# Backplane_Reference_R1_0.net
KiCad netlist of a schematic drawn in EAGLE
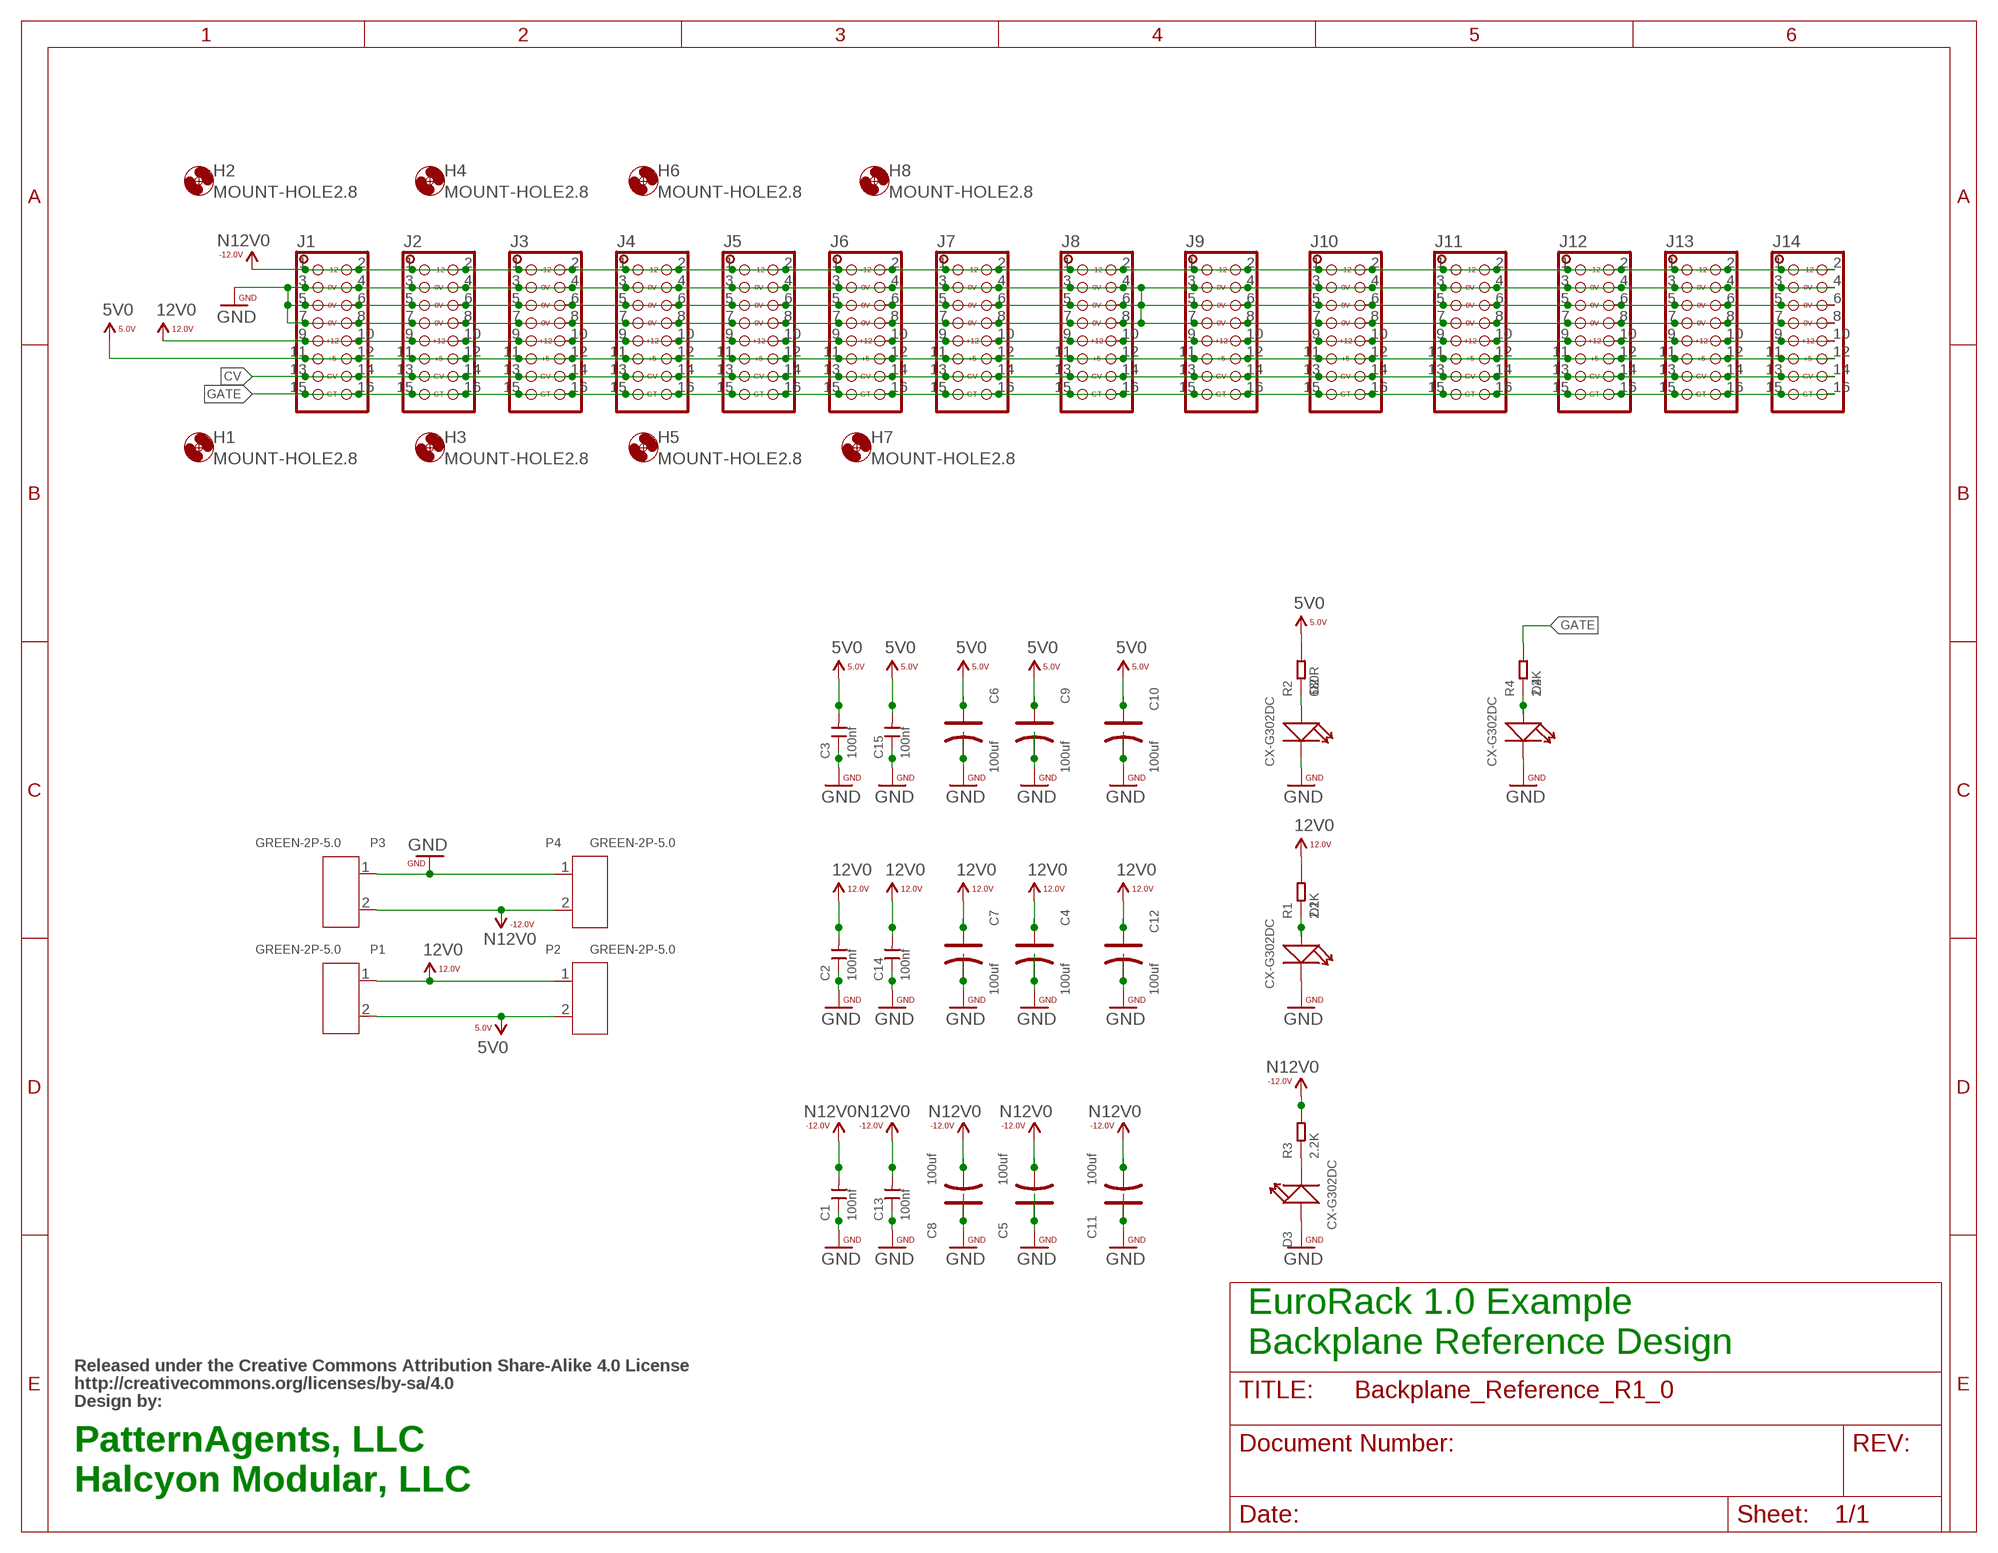
[diagram p0: schematic, sheet 1]

(export (version "E")
  (design (tool "Eeschema 10.0.6"))
  (components
    (comp (ref "C1")
      (value "100nf")
      (footprint "eagle-import:CERAMIC-2.54")
      (fields (field (name "MPN") "CC1-F5SL2A101KSPW"))
      (libsource (lib "eagle-import") (part "DIP-CERAMIC-DISC-100NF-50V-Y5V(D5.0MM)"))
    )
    (comp (ref "C2")
      (value "100nf")
      (footprint "eagle-import:CERAMIC-2.54")
      (fields (field (name "MPN") "CC1-F5SL2A101KSPW"))
      (libsource (lib "eagle-import") (part "DIP-CERAMIC-DISC-100NF-50V-Y5V(D5.0MM)"))
    )
    (comp (ref "C3")
      (value "100nf")
      (footprint "eagle-import:CERAMIC-2.54")
      (fields (field (name "MPN") "CC1-F5SL2A101KSPW"))
      (libsource (lib "eagle-import") (part "DIP-CERAMIC-DISC-100NF-50V-Y5V(D5.0MM)"))
    )
    (comp (ref "C4")
      (value "100uf")
      (footprint "eagle-import:PC-D5.3MM")
      (fields (field (name "MPN") "KS 100uF/16V"))
      (libsource (lib "eagle-import") (part "DIP-ALUMINUM-100UF-16V(D5-H7MM)"))
    )
    (comp (ref "C5")
      (value "100uf")
      (footprint "eagle-import:PC-D5.3MM")
      (fields (field (name "MPN") "KS 100uF/16V"))
      (libsource (lib "eagle-import") (part "DIP-ALUMINUM-100UF-16V(D5-H7MM)"))
    )
    (comp (ref "C6")
      (value "100uf")
      (footprint "eagle-import:PC-D5.3MM")
      (fields (field (name "MPN") "KS 100uF/16V"))
      (libsource (lib "eagle-import") (part "DIP-ALUMINUM-100UF-16V(D5-H7MM)"))
    )
    (comp (ref "C7")
      (value "100uf")
      (footprint "eagle-import:PC-D5.3MM")
      (fields (field (name "MPN") "KS 100uF/16V"))
      (libsource (lib "eagle-import") (part "DIP-ALUMINUM-100UF-16V(D5-H7MM)"))
    )
    (comp (ref "C8")
      (value "100uf")
      (footprint "eagle-import:PC-D5.3MM")
      (fields (field (name "MPN") "KS 100uF/16V"))
      (libsource (lib "eagle-import") (part "DIP-ALUMINUM-100UF-16V(D5-H7MM)"))
    )
    (comp (ref "C9")
      (value "100uf")
      (footprint "eagle-import:PC-D5.3MM")
      (fields (field (name "MPN") "KS 100uF/16V"))
      (libsource (lib "eagle-import") (part "DIP-ALUMINUM-100UF-16V(D5-H7MM)"))
    )
    (comp (ref "C10")
      (value "100uf")
      (footprint "eagle-import:PC-D5.3MM")
      (fields (field (name "MPN") "KS 100uF/16V"))
      (libsource (lib "eagle-import") (part "DIP-ALUMINUM-100UF-16V(D5-H7MM)"))
    )
    (comp (ref "C11")
      (value "100uf")
      (footprint "eagle-import:PC-D5.3MM")
      (fields (field (name "MPN") "KS 100uF/16V"))
      (libsource (lib "eagle-import") (part "DIP-ALUMINUM-100UF-16V(D5-H7MM)"))
    )
    (comp (ref "C12")
      (value "100uf")
      (footprint "eagle-import:PC-D5.3MM")
      (fields (field (name "MPN") "KS 100uF/16V"))
      (libsource (lib "eagle-import") (part "DIP-ALUMINUM-100UF-16V(D5-H7MM)"))
    )
    (comp (ref "C13")
      (value "100nf")
      (footprint "eagle-import:CERAMIC-2.54")
      (fields (field (name "MPN") "CC1-F5SL2A101KSPW"))
      (libsource (lib "eagle-import") (part "DIP-CERAMIC-DISC-100NF-50V-Y5V(D5.0MM)"))
    )
    (comp (ref "C14")
      (value "100nf")
      (footprint "eagle-import:CERAMIC-2.54")
      (fields (field (name "MPN") "CC1-F5SL2A101KSPW"))
      (libsource (lib "eagle-import") (part "DIP-CERAMIC-DISC-100NF-50V-Y5V(D5.0MM)"))
    )
    (comp (ref "C15")
      (value "100nf")
      (footprint "eagle-import:CERAMIC-2.54")
      (fields (field (name "MPN") "CC1-F5SL2A101KSPW"))
      (libsource (lib "eagle-import") (part "DIP-CERAMIC-DISC-100NF-50V-Y5V(D5.0MM)"))
    )
    (comp (ref "D1")
      (value "CX-G302DC")
      (footprint "eagle-import:LED2-2.54-D3.0MM")
      (libsource (lib "eagle-import") (part "DIP-LED-GREEN-GREEN(2P-D3MM)"))
    )
    (comp (ref "D2")
      (value "CX-G302DC")
      (footprint "eagle-import:LED2-2.54-D3.0MM")
      (libsource (lib "eagle-import") (part "DIP-LED-GREEN-GREEN(2P-D3MM)"))
    )
    (comp (ref "D3")
      (value "CX-G302DC")
      (footprint "eagle-import:LED2-2.54-D3.0MM")
      (libsource (lib "eagle-import") (part "DIP-LED-GREEN-GREEN(2P-D3MM)"))
    )
    (comp (ref "D4")
      (value "CX-G302DC")
      (footprint "eagle-import:LED2-2.54-D3.0MM")
      (libsource (lib "eagle-import") (part "DIP-LED-GREEN-GREEN(2P-D3MM)"))
    )
    (comp (ref "H1")
      (value "MOUNT-HOLE2.8")
      (footprint "eagle-import:2,8")
      (libsource (lib "eagle-import") (part "MOUNT-HOLE2.8"))
    )
    (comp (ref "H2")
      (value "MOUNT-HOLE2.8")
      (footprint "eagle-import:2,8")
      (libsource (lib "eagle-import") (part "MOUNT-HOLE2.8"))
    )
    (comp (ref "H3")
      (value "MOUNT-HOLE2.8")
      (footprint "eagle-import:2,8")
      (libsource (lib "eagle-import") (part "MOUNT-HOLE2.8"))
    )
    (comp (ref "H4")
      (value "MOUNT-HOLE2.8")
      (footprint "eagle-import:2,8")
      (libsource (lib "eagle-import") (part "MOUNT-HOLE2.8"))
    )
    (comp (ref "H5")
      (value "MOUNT-HOLE2.8")
      (footprint "eagle-import:2,8")
      (libsource (lib "eagle-import") (part "MOUNT-HOLE2.8"))
    )
    (comp (ref "H6")
      (value "MOUNT-HOLE2.8")
      (footprint "eagle-import:2,8")
      (libsource (lib "eagle-import") (part "MOUNT-HOLE2.8"))
    )
    (comp (ref "H7")
      (value "MOUNT-HOLE2.8")
      (footprint "eagle-import:2,8")
      (libsource (lib "eagle-import") (part "MOUNT-HOLE2.8"))
    )
    (comp (ref "H8")
      (value "MOUNT-HOLE2.8")
      (footprint "eagle-import:2,8")
      (libsource (lib "eagle-import") (part "MOUNT-HOLE2.8"))
    )
    (comp (ref "J1")
      (value "EUROPWR_2X08-SHROUD")
      (footprint "eagle-import:2X08_EUROPWR_SHROUD")
      (libsource (lib "eagle-import") (part "EUROPWR_2X08-SHROUD"))
    )
    (comp (ref "J2")
      (value "EUROPWR_2X08-SHROUD")
      (footprint "eagle-import:2X08_EUROPWR_SHROUD")
      (libsource (lib "eagle-import") (part "EUROPWR_2X08-SHROUD"))
    )
    (comp (ref "J3")
      (value "EUROPWR_2X08-SHROUD")
      (footprint "eagle-import:2X08_EUROPWR_SHROUD")
      (libsource (lib "eagle-import") (part "EUROPWR_2X08-SHROUD"))
    )
    (comp (ref "J4")
      (value "EUROPWR_2X08-SHROUD")
      (footprint "eagle-import:2X08_EUROPWR_SHROUD")
      (libsource (lib "eagle-import") (part "EUROPWR_2X08-SHROUD"))
    )
    (comp (ref "J5")
      (value "EUROPWR_2X08-SHROUD")
      (footprint "eagle-import:2X08_EUROPWR_SHROUD")
      (libsource (lib "eagle-import") (part "EUROPWR_2X08-SHROUD"))
    )
    (comp (ref "J6")
      (value "EUROPWR_2X08-SHROUD")
      (footprint "eagle-import:2X08_EUROPWR_SHROUD")
      (libsource (lib "eagle-import") (part "EUROPWR_2X08-SHROUD"))
    )
    (comp (ref "J7")
      (value "EUROPWR_2X08-SHROUD")
      (footprint "eagle-import:2X08_EUROPWR_SHROUD")
      (libsource (lib "eagle-import") (part "EUROPWR_2X08-SHROUD"))
    )
    (comp (ref "J8")
      (value "EUROPWR_2X08-SHROUD")
      (footprint "eagle-import:2X08_EUROPWR_SHROUD")
      (libsource (lib "eagle-import") (part "EUROPWR_2X08-SHROUD"))
    )
    (comp (ref "J9")
      (value "EUROPWR_2X08-SHROUD")
      (footprint "eagle-import:2X08_EUROPWR_SHROUD")
      (libsource (lib "eagle-import") (part "EUROPWR_2X08-SHROUD"))
    )
    (comp (ref "J10")
      (value "EUROPWR_2X08-SHROUD")
      (footprint "eagle-import:2X08_EUROPWR_SHROUD")
      (libsource (lib "eagle-import") (part "EUROPWR_2X08-SHROUD"))
    )
    (comp (ref "J11")
      (value "EUROPWR_2X08-SHROUD")
      (footprint "eagle-import:2X08_EUROPWR_SHROUD")
      (libsource (lib "eagle-import") (part "EUROPWR_2X08-SHROUD"))
    )
    (comp (ref "J12")
      (value "EUROPWR_2X08-SHROUD")
      (footprint "eagle-import:2X08_EUROPWR_SHROUD")
      (libsource (lib "eagle-import") (part "EUROPWR_2X08-SHROUD"))
    )
    (comp (ref "J13")
      (value "EUROPWR_2X08-SHROUD")
      (footprint "eagle-import:2X08_EUROPWR_SHROUD")
      (libsource (lib "eagle-import") (part "EUROPWR_2X08-SHROUD"))
    )
    (comp (ref "J14")
      (value "EUROPWR_2X08-SHROUD")
      (footprint "eagle-import:2X08_EUROPWR_SHROUD")
      (libsource (lib "eagle-import") (part "EUROPWR_2X08-SHROUD"))
    )
    (comp (ref "P1")
      (value "GREEN-2P-5.0")
      (footprint "eagle-import:H2-5.0-10.5X8.0MM")
      (libsource (lib "eagle-import") (part "SCREW-TERMINAL-GREEN(2P-5.0)"))
    )
    (comp (ref "P2")
      (value "GREEN-2P-5.0")
      (footprint "eagle-import:H2-5.0-10.5X8.0MM")
      (libsource (lib "eagle-import") (part "SCREW-TERMINAL-GREEN(2P-5.0)"))
    )
    (comp (ref "P3")
      (value "GREEN-2P-5.0")
      (footprint "eagle-import:H2-5.0-10.5X8.0MM")
      (libsource (lib "eagle-import") (part "SCREW-TERMINAL-GREEN(2P-5.0)"))
    )
    (comp (ref "P4")
      (value "GREEN-2P-5.0")
      (footprint "eagle-import:H2-5.0-10.5X8.0MM")
      (libsource (lib "eagle-import") (part "SCREW-TERMINAL-GREEN(2P-5.0)"))
    )
    (comp (ref "R1")
      (value "2.2K")
      (footprint "eagle-import:PR-D2.3XL6.5MM")
      (fields (field (name "MPN") "FHCFR-1/4W-222J"))
      (libsource (lib "eagle-import") (part "DIP-RES-2.2K-5%-1/4W(PR-D2.3XL6.5MM)"))
    )
    (comp (ref "R2")
      (value "680R")
      (footprint "eagle-import:PR-D2.3XL6.5MM")
      (fields (field (name "MPN") "FHCFR-1/4W-681J"))
      (libsource (lib "eagle-import") (part "DIP-RES-680R-5%-1/4W(PR-D2.3XL6.5MM)"))
    )
    (comp (ref "R3")
      (value "2.2K")
      (footprint "eagle-import:PR-D2.3XL6.5MM")
      (fields (field (name "MPN") "FHCFR-1/4W-222J"))
      (libsource (lib "eagle-import") (part "DIP-RES-2.2K-5%-1/4W(PR-D2.3XL6.5MM)"))
    )
    (comp (ref "R4")
      (value "2.2K")
      (footprint "eagle-import:PR-D2.3XL6.5MM")
      (fields (field (name "MPN") "FHCFR-1/4W-222J"))
      (libsource (lib "eagle-import") (part "DIP-RES-2.2K-5%-1/4W(PR-D2.3XL6.5MM)"))
    )
    (comp (ref "U$48")
      (value "BY_CC_SA_TEXTTEXT")
      (footprint "eagle-import:BY_CC_SA_TEXT")
      (libsource (lib "eagle-import") (part "BY_CC_SA_TEXTTEXT"))
    )
  )
  (nets
    (net (code "1") (name "5V0") (class "Default")
      (node (ref "C10") (pin "+") (pinfunction "+_+") (pintype "passive"))
      (node (ref "C15") (pin "2") (pinfunction "2_2") (pintype "passive"))
      (node (ref "C3") (pin "2") (pinfunction "2_2") (pintype "passive"))
      (node (ref "C6") (pin "+") (pinfunction "+_+") (pintype "passive"))
      (node (ref "C9") (pin "+") (pinfunction "+_+") (pintype "passive"))
      (node (ref "J1") (pin "11") (pinfunction "11_11") (pintype "passive"))
      (node (ref "J1") (pin "12") (pinfunction "12_12") (pintype "passive"))
      (node (ref "J10") (pin "11") (pinfunction "11_11") (pintype "passive"))
      (node (ref "J10") (pin "12") (pinfunction "12_12") (pintype "passive"))
      (node (ref "J11") (pin "11") (pinfunction "11_11") (pintype "passive"))
      (node (ref "J11") (pin "12") (pinfunction "12_12") (pintype "passive"))
      (node (ref "J12") (pin "11") (pinfunction "11_11") (pintype "passive"))
      (node (ref "J12") (pin "12") (pinfunction "12_12") (pintype "passive"))
      (node (ref "J13") (pin "11") (pinfunction "11_11") (pintype "passive"))
      (node (ref "J13") (pin "12") (pinfunction "12_12") (pintype "passive"))
      (node (ref "J14") (pin "11") (pinfunction "11_11") (pintype "passive"))
      (node (ref "J14") (pin "12") (pinfunction "12_12") (pintype "passive"))
      (node (ref "J2") (pin "11") (pinfunction "11_11") (pintype "passive"))
      (node (ref "J2") (pin "12") (pinfunction "12_12") (pintype "passive"))
      (node (ref "J3") (pin "11") (pinfunction "11_11") (pintype "passive"))
      (node (ref "J3") (pin "12") (pinfunction "12_12") (pintype "passive"))
      (node (ref "J4") (pin "11") (pinfunction "11_11") (pintype "passive"))
      (node (ref "J4") (pin "12") (pinfunction "12_12") (pintype "passive"))
      (node (ref "J5") (pin "11") (pinfunction "11_11") (pintype "passive"))
      (node (ref "J5") (pin "12") (pinfunction "12_12") (pintype "passive"))
      (node (ref "J6") (pin "11") (pinfunction "11_11") (pintype "passive"))
      (node (ref "J6") (pin "12") (pinfunction "12_12") (pintype "passive"))
      (node (ref "J7") (pin "11") (pinfunction "11_11") (pintype "passive"))
      (node (ref "J7") (pin "12") (pinfunction "12_12") (pintype "passive"))
      (node (ref "J8") (pin "11") (pinfunction "11_11") (pintype "passive"))
      (node (ref "J8") (pin "12") (pinfunction "12_12") (pintype "passive"))
      (node (ref "J9") (pin "11") (pinfunction "11_11") (pintype "passive"))
      (node (ref "J9") (pin "12") (pinfunction "12_12") (pintype "passive"))
      (node (ref "P1") (pin "2") (pinfunction "2_2") (pintype "bidirectional"))
      (node (ref "P2") (pin "2") (pinfunction "2_2") (pintype "bidirectional"))
      (node (ref "R2") (pin "2") (pinfunction "2_2") (pintype "passive"))
    )
    (net (code "2") (name "12V0") (class "Default")
      (node (ref "C12") (pin "+") (pinfunction "+_+") (pintype "passive"))
      (node (ref "C14") (pin "2") (pinfunction "2_2") (pintype "passive"))
      (node (ref "C2") (pin "2") (pinfunction "2_2") (pintype "passive"))
      (node (ref "C4") (pin "+") (pinfunction "+_+") (pintype "passive"))
      (node (ref "C7") (pin "+") (pinfunction "+_+") (pintype "passive"))
      (node (ref "J1") (pin "10") (pinfunction "10_10") (pintype "passive"))
      (node (ref "J1") (pin "9") (pinfunction "9_9") (pintype "passive"))
      (node (ref "J10") (pin "10") (pinfunction "10_10") (pintype "passive"))
      (node (ref "J10") (pin "9") (pinfunction "9_9") (pintype "passive"))
      (node (ref "J11") (pin "10") (pinfunction "10_10") (pintype "passive"))
      (node (ref "J11") (pin "9") (pinfunction "9_9") (pintype "passive"))
      (node (ref "J12") (pin "10") (pinfunction "10_10") (pintype "passive"))
      (node (ref "J12") (pin "9") (pinfunction "9_9") (pintype "passive"))
      (node (ref "J13") (pin "10") (pinfunction "10_10") (pintype "passive"))
      (node (ref "J13") (pin "9") (pinfunction "9_9") (pintype "passive"))
      (node (ref "J14") (pin "10") (pinfunction "10_10") (pintype "passive"))
      (node (ref "J14") (pin "9") (pinfunction "9_9") (pintype "passive"))
      (node (ref "J2") (pin "10") (pinfunction "10_10") (pintype "passive"))
      (node (ref "J2") (pin "9") (pinfunction "9_9") (pintype "passive"))
      (node (ref "J3") (pin "10") (pinfunction "10_10") (pintype "passive"))
      (node (ref "J3") (pin "9") (pinfunction "9_9") (pintype "passive"))
      (node (ref "J4") (pin "10") (pinfunction "10_10") (pintype "passive"))
      (node (ref "J4") (pin "9") (pinfunction "9_9") (pintype "passive"))
      (node (ref "J5") (pin "10") (pinfunction "10_10") (pintype "passive"))
      (node (ref "J5") (pin "9") (pinfunction "9_9") (pintype "passive"))
      (node (ref "J6") (pin "10") (pinfunction "10_10") (pintype "passive"))
      (node (ref "J6") (pin "9") (pinfunction "9_9") (pintype "passive"))
      (node (ref "J7") (pin "10") (pinfunction "10_10") (pintype "passive"))
      (node (ref "J7") (pin "9") (pinfunction "9_9") (pintype "passive"))
      (node (ref "J8") (pin "10") (pinfunction "10_10") (pintype "passive"))
      (node (ref "J8") (pin "9") (pinfunction "9_9") (pintype "passive"))
      (node (ref "J9") (pin "10") (pinfunction "10_10") (pintype "passive"))
      (node (ref "J9") (pin "9") (pinfunction "9_9") (pintype "passive"))
      (node (ref "P1") (pin "1") (pinfunction "1_1") (pintype "bidirectional"))
      (node (ref "P2") (pin "1") (pinfunction "1_1") (pintype "bidirectional"))
      (node (ref "R1") (pin "2") (pinfunction "2_2") (pintype "passive"))
    )
    (net (code "3") (name "CV") (class "Default")
      (node (ref "J1") (pin "13") (pinfunction "13_13") (pintype "passive"))
      (node (ref "J1") (pin "14") (pinfunction "14_14") (pintype "passive"))
      (node (ref "J10") (pin "13") (pinfunction "13_13") (pintype "passive"))
      (node (ref "J10") (pin "14") (pinfunction "14_14") (pintype "passive"))
      (node (ref "J11") (pin "13") (pinfunction "13_13") (pintype "passive"))
      (node (ref "J11") (pin "14") (pinfunction "14_14") (pintype "passive"))
      (node (ref "J12") (pin "13") (pinfunction "13_13") (pintype "passive"))
      (node (ref "J12") (pin "14") (pinfunction "14_14") (pintype "passive"))
      (node (ref "J13") (pin "13") (pinfunction "13_13") (pintype "passive"))
      (node (ref "J13") (pin "14") (pinfunction "14_14") (pintype "passive"))
      (node (ref "J14") (pin "13") (pinfunction "13_13") (pintype "passive"))
      (node (ref "J14") (pin "14") (pinfunction "14_14") (pintype "passive"))
      (node (ref "J2") (pin "13") (pinfunction "13_13") (pintype "passive"))
      (node (ref "J2") (pin "14") (pinfunction "14_14") (pintype "passive"))
      (node (ref "J3") (pin "13") (pinfunction "13_13") (pintype "passive"))
      (node (ref "J3") (pin "14") (pinfunction "14_14") (pintype "passive"))
      (node (ref "J4") (pin "13") (pinfunction "13_13") (pintype "passive"))
      (node (ref "J4") (pin "14") (pinfunction "14_14") (pintype "passive"))
      (node (ref "J5") (pin "13") (pinfunction "13_13") (pintype "passive"))
      (node (ref "J5") (pin "14") (pinfunction "14_14") (pintype "passive"))
      (node (ref "J6") (pin "13") (pinfunction "13_13") (pintype "passive"))
      (node (ref "J6") (pin "14") (pinfunction "14_14") (pintype "passive"))
      (node (ref "J7") (pin "13") (pinfunction "13_13") (pintype "passive"))
      (node (ref "J7") (pin "14") (pinfunction "14_14") (pintype "passive"))
      (node (ref "J8") (pin "13") (pinfunction "13_13") (pintype "passive"))
      (node (ref "J8") (pin "14") (pinfunction "14_14") (pintype "passive"))
      (node (ref "J9") (pin "13") (pinfunction "13_13") (pintype "passive"))
      (node (ref "J9") (pin "14") (pinfunction "14_14") (pintype "passive"))
    )
    (net (code "4") (name "GATE") (class "Default")
      (node (ref "J1") (pin "15") (pinfunction "15_15") (pintype "passive"))
      (node (ref "J1") (pin "16") (pinfunction "16_16") (pintype "passive"))
      (node (ref "J10") (pin "15") (pinfunction "15_15") (pintype "passive"))
      (node (ref "J10") (pin "16") (pinfunction "16_16") (pintype "passive"))
      (node (ref "J11") (pin "15") (pinfunction "15_15") (pintype "passive"))
      (node (ref "J11") (pin "16") (pinfunction "16_16") (pintype "passive"))
      (node (ref "J12") (pin "15") (pinfunction "15_15") (pintype "passive"))
      (node (ref "J12") (pin "16") (pinfunction "16_16") (pintype "passive"))
      (node (ref "J13") (pin "15") (pinfunction "15_15") (pintype "passive"))
      (node (ref "J13") (pin "16") (pinfunction "16_16") (pintype "passive"))
      (node (ref "J14") (pin "15") (pinfunction "15_15") (pintype "passive"))
      (node (ref "J14") (pin "16") (pinfunction "16_16") (pintype "passive"))
      (node (ref "J2") (pin "15") (pinfunction "15_15") (pintype "passive"))
      (node (ref "J2") (pin "16") (pinfunction "16_16") (pintype "passive"))
      (node (ref "J3") (pin "15") (pinfunction "15_15") (pintype "passive"))
      (node (ref "J3") (pin "16") (pinfunction "16_16") (pintype "passive"))
      (node (ref "J4") (pin "15") (pinfunction "15_15") (pintype "passive"))
      (node (ref "J4") (pin "16") (pinfunction "16_16") (pintype "passive"))
      (node (ref "J5") (pin "15") (pinfunction "15_15") (pintype "passive"))
      (node (ref "J5") (pin "16") (pinfunction "16_16") (pintype "passive"))
      (node (ref "J6") (pin "15") (pinfunction "15_15") (pintype "passive"))
      (node (ref "J6") (pin "16") (pinfunction "16_16") (pintype "passive"))
      (node (ref "J7") (pin "15") (pinfunction "15_15") (pintype "passive"))
      (node (ref "J7") (pin "16") (pinfunction "16_16") (pintype "passive"))
      (node (ref "J8") (pin "15") (pinfunction "15_15") (pintype "passive"))
      (node (ref "J8") (pin "16") (pinfunction "16_16") (pintype "passive"))
      (node (ref "J9") (pin "15") (pinfunction "15_15") (pintype "passive"))
      (node (ref "J9") (pin "16") (pinfunction "16_16") (pintype "passive"))
      (node (ref "R4") (pin "2") (pinfunction "2_2") (pintype "passive"))
    )
    (net (code "5") (name "GND") (class "Default")
      (node (ref "C1") (pin "1") (pinfunction "1_1") (pintype "passive"))
      (node (ref "C10") (pin "-") (pinfunction "-_-") (pintype "passive"))
      (node (ref "C11") (pin "+") (pinfunction "+_+") (pintype "passive"))
      (node (ref "C12") (pin "-") (pinfunction "-_-") (pintype "passive"))
      (node (ref "C13") (pin "1") (pinfunction "1_1") (pintype "passive"))
      (node (ref "C14") (pin "1") (pinfunction "1_1") (pintype "passive"))
      (node (ref "C15") (pin "1") (pinfunction "1_1") (pintype "passive"))
      (node (ref "C2") (pin "1") (pinfunction "1_1") (pintype "passive"))
      (node (ref "C3") (pin "1") (pinfunction "1_1") (pintype "passive"))
      (node (ref "C4") (pin "-") (pinfunction "-_-") (pintype "passive"))
      (node (ref "C5") (pin "+") (pinfunction "+_+") (pintype "passive"))
      (node (ref "C6") (pin "-") (pinfunction "-_-") (pintype "passive"))
      (node (ref "C7") (pin "-") (pinfunction "-_-") (pintype "passive"))
      (node (ref "C8") (pin "+") (pinfunction "+_+") (pintype "passive"))
      (node (ref "C9") (pin "-") (pinfunction "-_-") (pintype "passive"))
      (node (ref "D1") (pin "K") (pinfunction "-_K") (pintype "passive"))
      (node (ref "D2") (pin "K") (pinfunction "-_K") (pintype "passive"))
      (node (ref "D3") (pin "A") (pinfunction "+_A") (pintype "passive"))
      (node (ref "D4") (pin "K") (pinfunction "-_K") (pintype "passive"))
      (node (ref "J1") (pin "3") (pinfunction "3_3") (pintype "passive"))
      (node (ref "J1") (pin "4") (pinfunction "4_4") (pintype "passive"))
      (node (ref "J1") (pin "5") (pinfunction "5_5") (pintype "passive"))
      (node (ref "J1") (pin "6") (pinfunction "6_6") (pintype "passive"))
      (node (ref "J1") (pin "7") (pinfunction "7_7") (pintype "passive"))
      (node (ref "J1") (pin "8") (pinfunction "8_8") (pintype "passive"))
      (node (ref "J10") (pin "3") (pinfunction "3_3") (pintype "passive"))
      (node (ref "J10") (pin "4") (pinfunction "4_4") (pintype "passive"))
      (node (ref "J10") (pin "5") (pinfunction "5_5") (pintype "passive"))
      (node (ref "J10") (pin "6") (pinfunction "6_6") (pintype "passive"))
      (node (ref "J10") (pin "7") (pinfunction "7_7") (pintype "passive"))
      (node (ref "J10") (pin "8") (pinfunction "8_8") (pintype "passive"))
      (node (ref "J11") (pin "3") (pinfunction "3_3") (pintype "passive"))
      (node (ref "J11") (pin "4") (pinfunction "4_4") (pintype "passive"))
      (node (ref "J11") (pin "5") (pinfunction "5_5") (pintype "passive"))
      (node (ref "J11") (pin "6") (pinfunction "6_6") (pintype "passive"))
      (node (ref "J11") (pin "7") (pinfunction "7_7") (pintype "passive"))
      (node (ref "J11") (pin "8") (pinfunction "8_8") (pintype "passive"))
      (node (ref "J12") (pin "3") (pinfunction "3_3") (pintype "passive"))
      (node (ref "J12") (pin "4") (pinfunction "4_4") (pintype "passive"))
      (node (ref "J12") (pin "5") (pinfunction "5_5") (pintype "passive"))
      (node (ref "J12") (pin "6") (pinfunction "6_6") (pintype "passive"))
      (node (ref "J12") (pin "7") (pinfunction "7_7") (pintype "passive"))
      (node (ref "J12") (pin "8") (pinfunction "8_8") (pintype "passive"))
      (node (ref "J13") (pin "3") (pinfunction "3_3") (pintype "passive"))
      (node (ref "J13") (pin "4") (pinfunction "4_4") (pintype "passive"))
      (node (ref "J13") (pin "5") (pinfunction "5_5") (pintype "passive"))
      (node (ref "J13") (pin "6") (pinfunction "6_6") (pintype "passive"))
      (node (ref "J13") (pin "7") (pinfunction "7_7") (pintype "passive"))
      (node (ref "J13") (pin "8") (pinfunction "8_8") (pintype "passive"))
      (node (ref "J14") (pin "3") (pinfunction "3_3") (pintype "passive"))
      (node (ref "J14") (pin "4") (pinfunction "4_4") (pintype "passive"))
      (node (ref "J14") (pin "5") (pinfunction "5_5") (pintype "passive"))
      (node (ref "J14") (pin "6") (pinfunction "6_6") (pintype "passive"))
      (node (ref "J14") (pin "7") (pinfunction "7_7") (pintype "passive"))
      (node (ref "J14") (pin "8") (pinfunction "8_8") (pintype "passive"))
      (node (ref "J2") (pin "3") (pinfunction "3_3") (pintype "passive"))
      (node (ref "J2") (pin "4") (pinfunction "4_4") (pintype "passive"))
      (node (ref "J2") (pin "5") (pinfunction "5_5") (pintype "passive"))
      (node (ref "J2") (pin "6") (pinfunction "6_6") (pintype "passive"))
      (node (ref "J2") (pin "7") (pinfunction "7_7") (pintype "passive"))
      (node (ref "J2") (pin "8") (pinfunction "8_8") (pintype "passive"))
      (node (ref "J3") (pin "3") (pinfunction "3_3") (pintype "passive"))
      (node (ref "J3") (pin "4") (pinfunction "4_4") (pintype "passive"))
      (node (ref "J3") (pin "5") (pinfunction "5_5") (pintype "passive"))
      (node (ref "J3") (pin "6") (pinfunction "6_6") (pintype "passive"))
      (node (ref "J3") (pin "7") (pinfunction "7_7") (pintype "passive"))
      (node (ref "J3") (pin "8") (pinfunction "8_8") (pintype "passive"))
      (node (ref "J4") (pin "3") (pinfunction "3_3") (pintype "passive"))
      (node (ref "J4") (pin "4") (pinfunction "4_4") (pintype "passive"))
      (node (ref "J4") (pin "5") (pinfunction "5_5") (pintype "passive"))
      (node (ref "J4") (pin "6") (pinfunction "6_6") (pintype "passive"))
      (node (ref "J4") (pin "7") (pinfunction "7_7") (pintype "passive"))
      (node (ref "J4") (pin "8") (pinfunction "8_8") (pintype "passive"))
      (node (ref "J5") (pin "3") (pinfunction "3_3") (pintype "passive"))
      (node (ref "J5") (pin "4") (pinfunction "4_4") (pintype "passive"))
      (node (ref "J5") (pin "5") (pinfunction "5_5") (pintype "passive"))
      (node (ref "J5") (pin "6") (pinfunction "6_6") (pintype "passive"))
      (node (ref "J5") (pin "7") (pinfunction "7_7") (pintype "passive"))
      (node (ref "J5") (pin "8") (pinfunction "8_8") (pintype "passive"))
      (node (ref "J6") (pin "3") (pinfunction "3_3") (pintype "passive"))
      (node (ref "J6") (pin "4") (pinfunction "4_4") (pintype "passive"))
      (node (ref "J6") (pin "5") (pinfunction "5_5") (pintype "passive"))
      (node (ref "J6") (pin "6") (pinfunction "6_6") (pintype "passive"))
      (node (ref "J6") (pin "7") (pinfunction "7_7") (pintype "passive"))
      (node (ref "J6") (pin "8") (pinfunction "8_8") (pintype "passive"))
      (node (ref "J7") (pin "3") (pinfunction "3_3") (pintype "passive"))
      (node (ref "J7") (pin "4") (pinfunction "4_4") (pintype "passive"))
      (node (ref "J7") (pin "5") (pinfunction "5_5") (pintype "passive"))
      (node (ref "J7") (pin "6") (pinfunction "6_6") (pintype "passive"))
      (node (ref "J7") (pin "7") (pinfunction "7_7") (pintype "passive"))
      (node (ref "J7") (pin "8") (pinfunction "8_8") (pintype "passive"))
      (node (ref "J8") (pin "3") (pinfunction "3_3") (pintype "passive"))
      (node (ref "J8") (pin "4") (pinfunction "4_4") (pintype "passive"))
      (node (ref "J8") (pin "5") (pinfunction "5_5") (pintype "passive"))
      (node (ref "J8") (pin "6") (pinfunction "6_6") (pintype "passive"))
      (node (ref "J8") (pin "7") (pinfunction "7_7") (pintype "passive"))
      (node (ref "J8") (pin "8") (pinfunction "8_8") (pintype "passive"))
      (node (ref "J9") (pin "3") (pinfunction "3_3") (pintype "passive"))
      (node (ref "J9") (pin "4") (pinfunction "4_4") (pintype "passive"))
      (node (ref "J9") (pin "5") (pinfunction "5_5") (pintype "passive"))
      (node (ref "J9") (pin "6") (pinfunction "6_6") (pintype "passive"))
      (node (ref "J9") (pin "7") (pinfunction "7_7") (pintype "passive"))
      (node (ref "J9") (pin "8") (pinfunction "8_8") (pintype "passive"))
      (node (ref "P3") (pin "1") (pinfunction "1_1") (pintype "bidirectional"))
      (node (ref "P4") (pin "1") (pinfunction "1_1") (pintype "bidirectional"))
    )
    (net (code "6") (name "N12V0") (class "Default")
      (node (ref "C1") (pin "2") (pinfunction "2_2") (pintype "passive"))
      (node (ref "C11") (pin "-") (pinfunction "-_-") (pintype "passive"))
      (node (ref "C13") (pin "2") (pinfunction "2_2") (pintype "passive"))
      (node (ref "C5") (pin "-") (pinfunction "-_-") (pintype "passive"))
      (node (ref "C8") (pin "-") (pinfunction "-_-") (pintype "passive"))
      (node (ref "J1") (pin "1") (pinfunction "1_1") (pintype "passive"))
      (node (ref "J1") (pin "2") (pinfunction "2_2") (pintype "passive"))
      (node (ref "J10") (pin "1") (pinfunction "1_1") (pintype "passive"))
      (node (ref "J10") (pin "2") (pinfunction "2_2") (pintype "passive"))
      (node (ref "J11") (pin "1") (pinfunction "1_1") (pintype "passive"))
      (node (ref "J11") (pin "2") (pinfunction "2_2") (pintype "passive"))
      (node (ref "J12") (pin "1") (pinfunction "1_1") (pintype "passive"))
      (node (ref "J12") (pin "2") (pinfunction "2_2") (pintype "passive"))
      (node (ref "J13") (pin "1") (pinfunction "1_1") (pintype "passive"))
      (node (ref "J13") (pin "2") (pinfunction "2_2") (pintype "passive"))
      (node (ref "J14") (pin "1") (pinfunction "1_1") (pintype "passive"))
      (node (ref "J14") (pin "2") (pinfunction "2_2") (pintype "passive"))
      (node (ref "J2") (pin "1") (pinfunction "1_1") (pintype "passive"))
      (node (ref "J2") (pin "2") (pinfunction "2_2") (pintype "passive"))
      (node (ref "J3") (pin "1") (pinfunction "1_1") (pintype "passive"))
      (node (ref "J3") (pin "2") (pinfunction "2_2") (pintype "passive"))
      (node (ref "J4") (pin "1") (pinfunction "1_1") (pintype "passive"))
      (node (ref "J4") (pin "2") (pinfunction "2_2") (pintype "passive"))
      (node (ref "J5") (pin "1") (pinfunction "1_1") (pintype "passive"))
      (node (ref "J5") (pin "2") (pinfunction "2_2") (pintype "passive"))
      (node (ref "J6") (pin "1") (pinfunction "1_1") (pintype "passive"))
      (node (ref "J6") (pin "2") (pinfunction "2_2") (pintype "passive"))
      (node (ref "J7") (pin "1") (pinfunction "1_1") (pintype "passive"))
      (node (ref "J7") (pin "2") (pinfunction "2_2") (pintype "passive"))
      (node (ref "J8") (pin "1") (pinfunction "1_1") (pintype "passive"))
      (node (ref "J8") (pin "2") (pinfunction "2_2") (pintype "passive"))
      (node (ref "J9") (pin "1") (pinfunction "1_1") (pintype "passive"))
      (node (ref "J9") (pin "2") (pinfunction "2_2") (pintype "passive"))
      (node (ref "P3") (pin "2") (pinfunction "2_2") (pintype "bidirectional"))
      (node (ref "P4") (pin "2") (pinfunction "2_2") (pintype "bidirectional"))
      (node (ref "R3") (pin "2") (pinfunction "2_2") (pintype "passive"))
    )
    (net (code "7") (name "Net-(D1-+)") (class "Default")
      (node (ref "D1") (pin "A") (pinfunction "+_A") (pintype "passive"))
      (node (ref "R1") (pin "1") (pinfunction "1_1") (pintype "passive"))
    )
    (net (code "8") (name "Net-(D2-+)") (class "Default")
      (node (ref "D2") (pin "A") (pinfunction "+_A") (pintype "passive"))
      (node (ref "R2") (pin "1") (pinfunction "1_1") (pintype "passive"))
    )
    (net (code "9") (name "Net-(D3--)") (class "Default")
      (node (ref "D3") (pin "K") (pinfunction "-_K") (pintype "passive"))
      (node (ref "R3") (pin "1") (pinfunction "1_1") (pintype "passive"))
    )
    (net (code "10") (name "Net-(D4-+)") (class "Default")
      (node (ref "D4") (pin "A") (pinfunction "+_A") (pintype "passive"))
      (node (ref "R4") (pin "1") (pinfunction "1_1") (pintype "passive"))
    )
  )
)
